# energy-monitor.net
KiCad netlist of a schematic drawn in Altium Designer
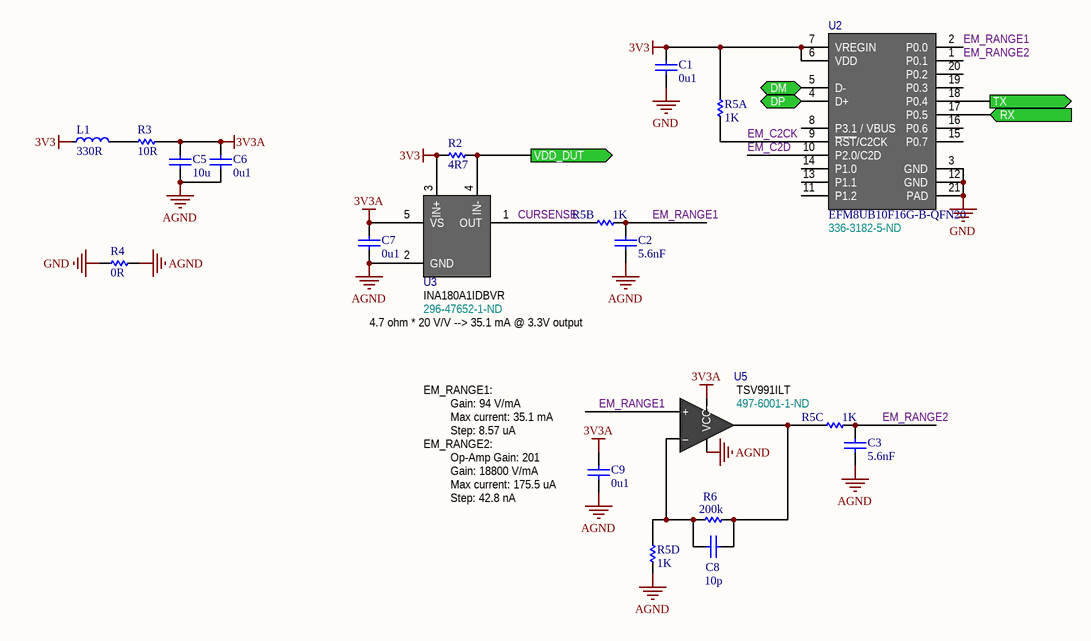
[diagram p0: energy-monitor.SchDoc]

(export (version "E")
  (design (tool "Eeschema 10.0.6"))
  (components
    (comp (ref "C1")
      (value "0u1")
      (footprint "CAPC1005N")
      (description "Capacitor (Semiconductor SIM Model)")
      (fields (field (name "PUBLISHER") "Altium Limited"))
      (libsource (lib "Miscellaneous Devices") (part "Cap Semi"))
    )
    (comp (ref "C2")
      (value "5.6nF")
      (footprint "CAPC1005N")
      (description "Capacitor (Semiconductor SIM Model)")
      (fields (field (name "PUBLISHER") "Altium Limited"))
      (libsource (lib "Miscellaneous Devices") (part "Cap Semi"))
    )
    (comp (ref "C3")
      (value "5.6nF")
      (footprint "CAPC1005N")
      (description "Capacitor (Semiconductor SIM Model)")
      (fields (field (name "PUBLISHER") "Altium Limited"))
      (libsource (lib "Miscellaneous Devices") (part "Cap Semi"))
    )
    (comp (ref "C5")
      (value "10u")
      (footprint "CAPC1608N")
      (description "Capacitor (Semiconductor SIM Model)")
      (fields (field (name "PUBLISHER") "Altium Limited"))
      (libsource (lib "Miscellaneous Devices") (part "Cap Semi"))
    )
    (comp (ref "C6")
      (value "0u1")
      (footprint "CAPC1005N")
      (description "Capacitor (Semiconductor SIM Model)")
      (fields (field (name "PUBLISHER") "Altium Limited"))
      (libsource (lib "Miscellaneous Devices") (part "Cap Semi"))
    )
    (comp (ref "C7")
      (value "0u1")
      (footprint "CAPC1005N")
      (description "Capacitor (Semiconductor SIM Model)")
      (fields (field (name "PUBLISHER") "Altium Limited"))
      (libsource (lib "Miscellaneous Devices") (part "Cap Semi"))
    )
    (comp (ref "C8")
      (value "10p")
      (footprint "CAPC1005N")
      (description "Capacitor (Semiconductor SIM Model)")
      (fields (field (name "PUBLISHER") "Altium Limited"))
      (libsource (lib "Miscellaneous Devices") (part "Cap Semi"))
    )
    (comp (ref "C9")
      (value "0u1")
      (footprint "CAPC1005N")
      (description "Capacitor (Semiconductor SIM Model)")
      (fields (field (name "PUBLISHER") "Altium Limited"))
      (libsource (lib "Miscellaneous Devices") (part "Cap Semi"))
    )
    (comp (ref "L1")
      (value "330R")
      (footprint "INDC1005N")
      (description "Inductor")
      (fields (field (name "PUBLISHER") "Altium Limited"))
      (libsource (lib "Miscellaneous Devices") (part "Inductor"))
    )
    (comp (ref "R2")
      (value "4R7")
      (footprint "RESC1608N")
      (description "Semiconductor Resistor")
      (fields (field (name "PUBLISHER") "Altium Limited"))
      (libsource (lib "Miscellaneous Devices") (part "Res Semi"))
    )
    (comp (ref "R3")
      (value "10R")
      (footprint "RESC1005N")
      (description "Semiconductor Resistor")
      (fields (field (name "PUBLISHER") "Altium Limited"))
      (libsource (lib "Miscellaneous Devices") (part "Res Semi"))
    )
    (comp (ref "R4")
      (value "0R")
      (footprint "RESC1005N")
      (description "Semiconductor Resistor")
      (fields (field (name "PUBLISHER") "Altium Limited"))
      (libsource (lib "Miscellaneous Devices") (part "Res Semi"))
    )
    (comp (ref "R5")
      (value "1K")
      (footprint "RESNET_8_1206")
      (description "Isolated Resistor Network - Parts")
      (fields (field (name "Comment") "Res Pack5") (field (name "PUBLISHER") "Altium Limited"))
      (libsource (lib "Miscellaneous Devices") (part "Res Pack5"))
    )
    (comp (ref "R6")
      (value "200k")
      (footprint "RESC1005N")
      (description "Semiconductor Resistor")
      (fields (field (name "PUBLISHER") "Altium Limited"))
      (libsource (lib "Miscellaneous Devices") (part "Res Semi"))
    )
    (comp (ref "U2")
      (value "EFM8UB10F16G-B-QFN20")
      (footprint "QFN50P300X300X90-20N")
      (description "IC MCU 16KB 20QFN")
      (fields
        (field (name "MANUFACTURER") "Silicon Labs")
        (field (name "SUPPLIER PART NUMBER 1") "336-3182-5-ND")
      )
      (libsource (lib "SiLabs 8-bit MCU") (part "EFM8UB10F16G-B-QFN20"))
    )
    (comp (ref "U3")
      (value "INA180A1IDBVR")
      (footprint "SOT23-5AN")
      (fields
        (field (name "MANUFACTURER") "Texas Instruments")
        (field (name "SUPPLIER PART NUMBER 1") "296-47652-1-ND")
      )
      (libsource (lib "TI Operational Amplifier") (part "INA180A1IDBVR"))
    )
    (comp (ref "U5")
      (value "TSV991ILT")
      (footprint "SOT23-5AN")
      (description "IC OPAMP GP 20MHZ RRO SOT23-5")
      (fields
        (field (name "MANUFACTURER") "STMicroelectronics")
        (field (name "BASE PART NUMBER") "TSV991")
        (field (name "SUPPLIER PART NUMBER 1") "497-6001-1-ND")
      )
      (libsource (lib "ST Operational Amplifier") (part "TSV991ILT"))
    )
  )
  (nets
    (net (code "1") (name "/CURSENSE") (class "Default")
      (node (ref "R5") (pin "7") (pinfunction "7_7") (pintype "passive"))
      (node (ref "U3") (pin "1") (pinfunction "OUT_1") (pintype "passive"))
    )
    (net (code "2") (name "/DM") (class "Default")
      (node (ref "U2") (pin "5") (pinfunction "D-_5") (pintype "passive"))
    )
    (net (code "3") (name "/DP") (class "Default")
      (node (ref "U2") (pin "4") (pinfunction "D+_4") (pintype "passive"))
    )
    (net (code "4") (name "/EM_C2CK") (class "Default")
      (node (ref "R5") (pin "1") (pinfunction "1_1") (pintype "passive"))
      (node (ref "U2") (pin "9") (pinfunction "~{RST}/C2CK_9") (pintype "passive"))
    )
    (net (code "5") (name "/EM_C2D") (class "Default")
      (node (ref "U2") (pin "10") (pinfunction "P2.0/C2D_10") (pintype "passive"))
    )
    (net (code "6") (name "/EM_RANGE1") (class "Default")
      (node (ref "C2") (pin "2") (pinfunction "2_2") (pintype "passive"))
      (node (ref "R5") (pin "2") (pinfunction "2_2") (pintype "passive"))
      (node (ref "U2") (pin "2") (pinfunction "P0.0_2") (pintype "passive"))
      (node (ref "U5") (pin "3") (pinfunction "+_3") (pintype "passive"))
    )
    (net (code "7") (name "/EM_RANGE2") (class "Default")
      (node (ref "C3") (pin "2") (pinfunction "2_2") (pintype "passive"))
      (node (ref "R5") (pin "3") (pinfunction "3_3") (pintype "passive"))
      (node (ref "U2") (pin "1") (pinfunction "P0.1_1") (pintype "passive"))
    )
    (net (code "8") (name "/RX") (class "Default")
      (node (ref "U2") (pin "17") (pinfunction "P0.5_17") (pintype "passive"))
    )
    (net (code "9") (name "/TX") (class "Default")
      (node (ref "U2") (pin "18") (pinfunction "P0.4_18") (pintype "passive"))
    )
    (net (code "10") (name "/VDD_DUT") (class "Default")
      (node (ref "R2") (pin "2") (pinfunction "2_2") (pintype "passive"))
      (node (ref "U3") (pin "4") (pinfunction "IN-_4") (pintype "passive"))
    )
    (net (code "11") (name "3V3") (class "Default")
      (node (ref "C1") (pin "2") (pinfunction "2_2") (pintype "passive"))
      (node (ref "L1") (pin "1") (pinfunction "1_1") (pintype "passive"))
      (node (ref "R2") (pin "1") (pinfunction "1_1") (pintype "passive"))
      (node (ref "R5") (pin "8") (pinfunction "8_8") (pintype "passive"))
      (node (ref "U2") (pin "6") (pinfunction "VDD_6") (pintype "passive"))
      (node (ref "U2") (pin "7") (pinfunction "VREGIN_7") (pintype "passive"))
      (node (ref "U3") (pin "3") (pinfunction "IN+_3") (pintype "passive"))
    )
    (net (code "12") (name "3V3A") (class "Default")
      (node (ref "C5") (pin "2") (pinfunction "2_2") (pintype "passive"))
      (node (ref "C6") (pin "2") (pinfunction "2_2") (pintype "passive"))
      (node (ref "C7") (pin "2") (pinfunction "2_2") (pintype "passive"))
      (node (ref "C9") (pin "2") (pinfunction "2_2") (pintype "passive"))
      (node (ref "R3") (pin "2") (pinfunction "2_2") (pintype "passive"))
      (node (ref "U3") (pin "5") (pinfunction "VS_5") (pintype "passive"))
      (node (ref "U5") (pin "5") (pinfunction "VCC+_5") (pintype "passive"))
    )
    (net (code "13") (name "AGND") (class "Default")
      (node (ref "C2") (pin "1") (pinfunction "1_1") (pintype "passive"))
      (node (ref "C3") (pin "1") (pinfunction "1_1") (pintype "passive"))
      (node (ref "C5") (pin "1") (pinfunction "1_1") (pintype "passive"))
      (node (ref "C6") (pin "1") (pinfunction "1_1") (pintype "passive"))
      (node (ref "C7") (pin "1") (pinfunction "1_1") (pintype "passive"))
      (node (ref "C9") (pin "1") (pinfunction "1_1") (pintype "passive"))
      (node (ref "R4") (pin "2") (pinfunction "2_2") (pintype "passive"))
      (node (ref "R5") (pin "5") (pinfunction "5_5") (pintype "passive"))
      (node (ref "U3") (pin "2") (pinfunction "GND_2") (pintype "passive"))
      (node (ref "U5") (pin "2") (pinfunction "VCC-_2") (pintype "passive"))
    )
    (net (code "14") (name "GND") (class "Default")
      (node (ref "C1") (pin "1") (pinfunction "1_1") (pintype "passive"))
      (node (ref "R4") (pin "1") (pinfunction "1_1") (pintype "passive"))
      (node (ref "U2") (pin "12") (pinfunction "GND_12") (pintype "passive"))
      (node (ref "U2") (pin "21") (pinfunction "PAD_21") (pintype "passive"))
      (node (ref "U2") (pin "3") (pinfunction "GND_3") (pintype "passive"))
    )
    (net (code "15") (name "Net-(L1-Pad2)") (class "Default")
      (node (ref "L1") (pin "2") (pinfunction "2_2") (pintype "passive"))
      (node (ref "R3") (pin "1") (pinfunction "1_1") (pintype "passive"))
    )
    (net (code "16") (name "Net-(U5-OUT)") (class "Default")
      (node (ref "C8") (pin "2") (pinfunction "2_2") (pintype "passive"))
      (node (ref "R5") (pin "6") (pinfunction "6_6") (pintype "passive"))
      (node (ref "R6") (pin "2") (pinfunction "2_2") (pintype "passive"))
      (node (ref "U5") (pin "1") (pinfunction "OUT_1") (pintype "passive"))
    )
    (net (code "17") (name "Net-(U5-–)") (class "Default")
      (node (ref "C8") (pin "1") (pinfunction "1_1") (pintype "passive"))
      (node (ref "R5") (pin "4") (pinfunction "4_4") (pintype "passive"))
      (node (ref "R6") (pin "1") (pinfunction "1_1") (pintype "passive"))
      (node (ref "U5") (pin "4") (pinfunction "–_4") (pintype "passive"))
    )
    (net (code "18") (name "unconnected-(U2-P0.2-Pad20)") (class "Default")
      (node (ref "U2") (pin "20") (pinfunction "P0.2_20") (pintype "passive"))
    )
    (net (code "19") (name "unconnected-(U2-P0.3-Pad19)") (class "Default")
      (node (ref "U2") (pin "19") (pinfunction "P0.3_19") (pintype "passive"))
    )
    (net (code "20") (name "unconnected-(U2-P0.6-Pad16)") (class "Default")
      (node (ref "U2") (pin "16") (pinfunction "P0.6_16") (pintype "passive"))
    )
    (net (code "21") (name "unconnected-(U2-P0.7-Pad15)") (class "Default")
      (node (ref "U2") (pin "15") (pinfunction "P0.7_15") (pintype "passive"))
    )
    (net (code "22") (name "unconnected-(U2-P1.0-Pad14)") (class "Default")
      (node (ref "U2") (pin "14") (pinfunction "P1.0_14") (pintype "passive"))
    )
    (net (code "23") (name "unconnected-(U2-P1.1-Pad13)") (class "Default")
      (node (ref "U2") (pin "13") (pinfunction "P1.1_13") (pintype "passive"))
    )
    (net (code "24") (name "unconnected-(U2-P1.2-Pad11)") (class "Default")
      (node (ref "U2") (pin "11") (pinfunction "P1.2_11") (pintype "passive"))
    )
    (net (code "25") (name "unconnected-(U2-P3.1_{slash}_VBUS-Pad8)") (class "Default")
      (node (ref "U2") (pin "8") (pinfunction "P3.1_/_VBUS_8") (pintype "passive"))
    )
  )
)
